# LCD.net
KiCad netlist of a schematic drawn in Altium Designer
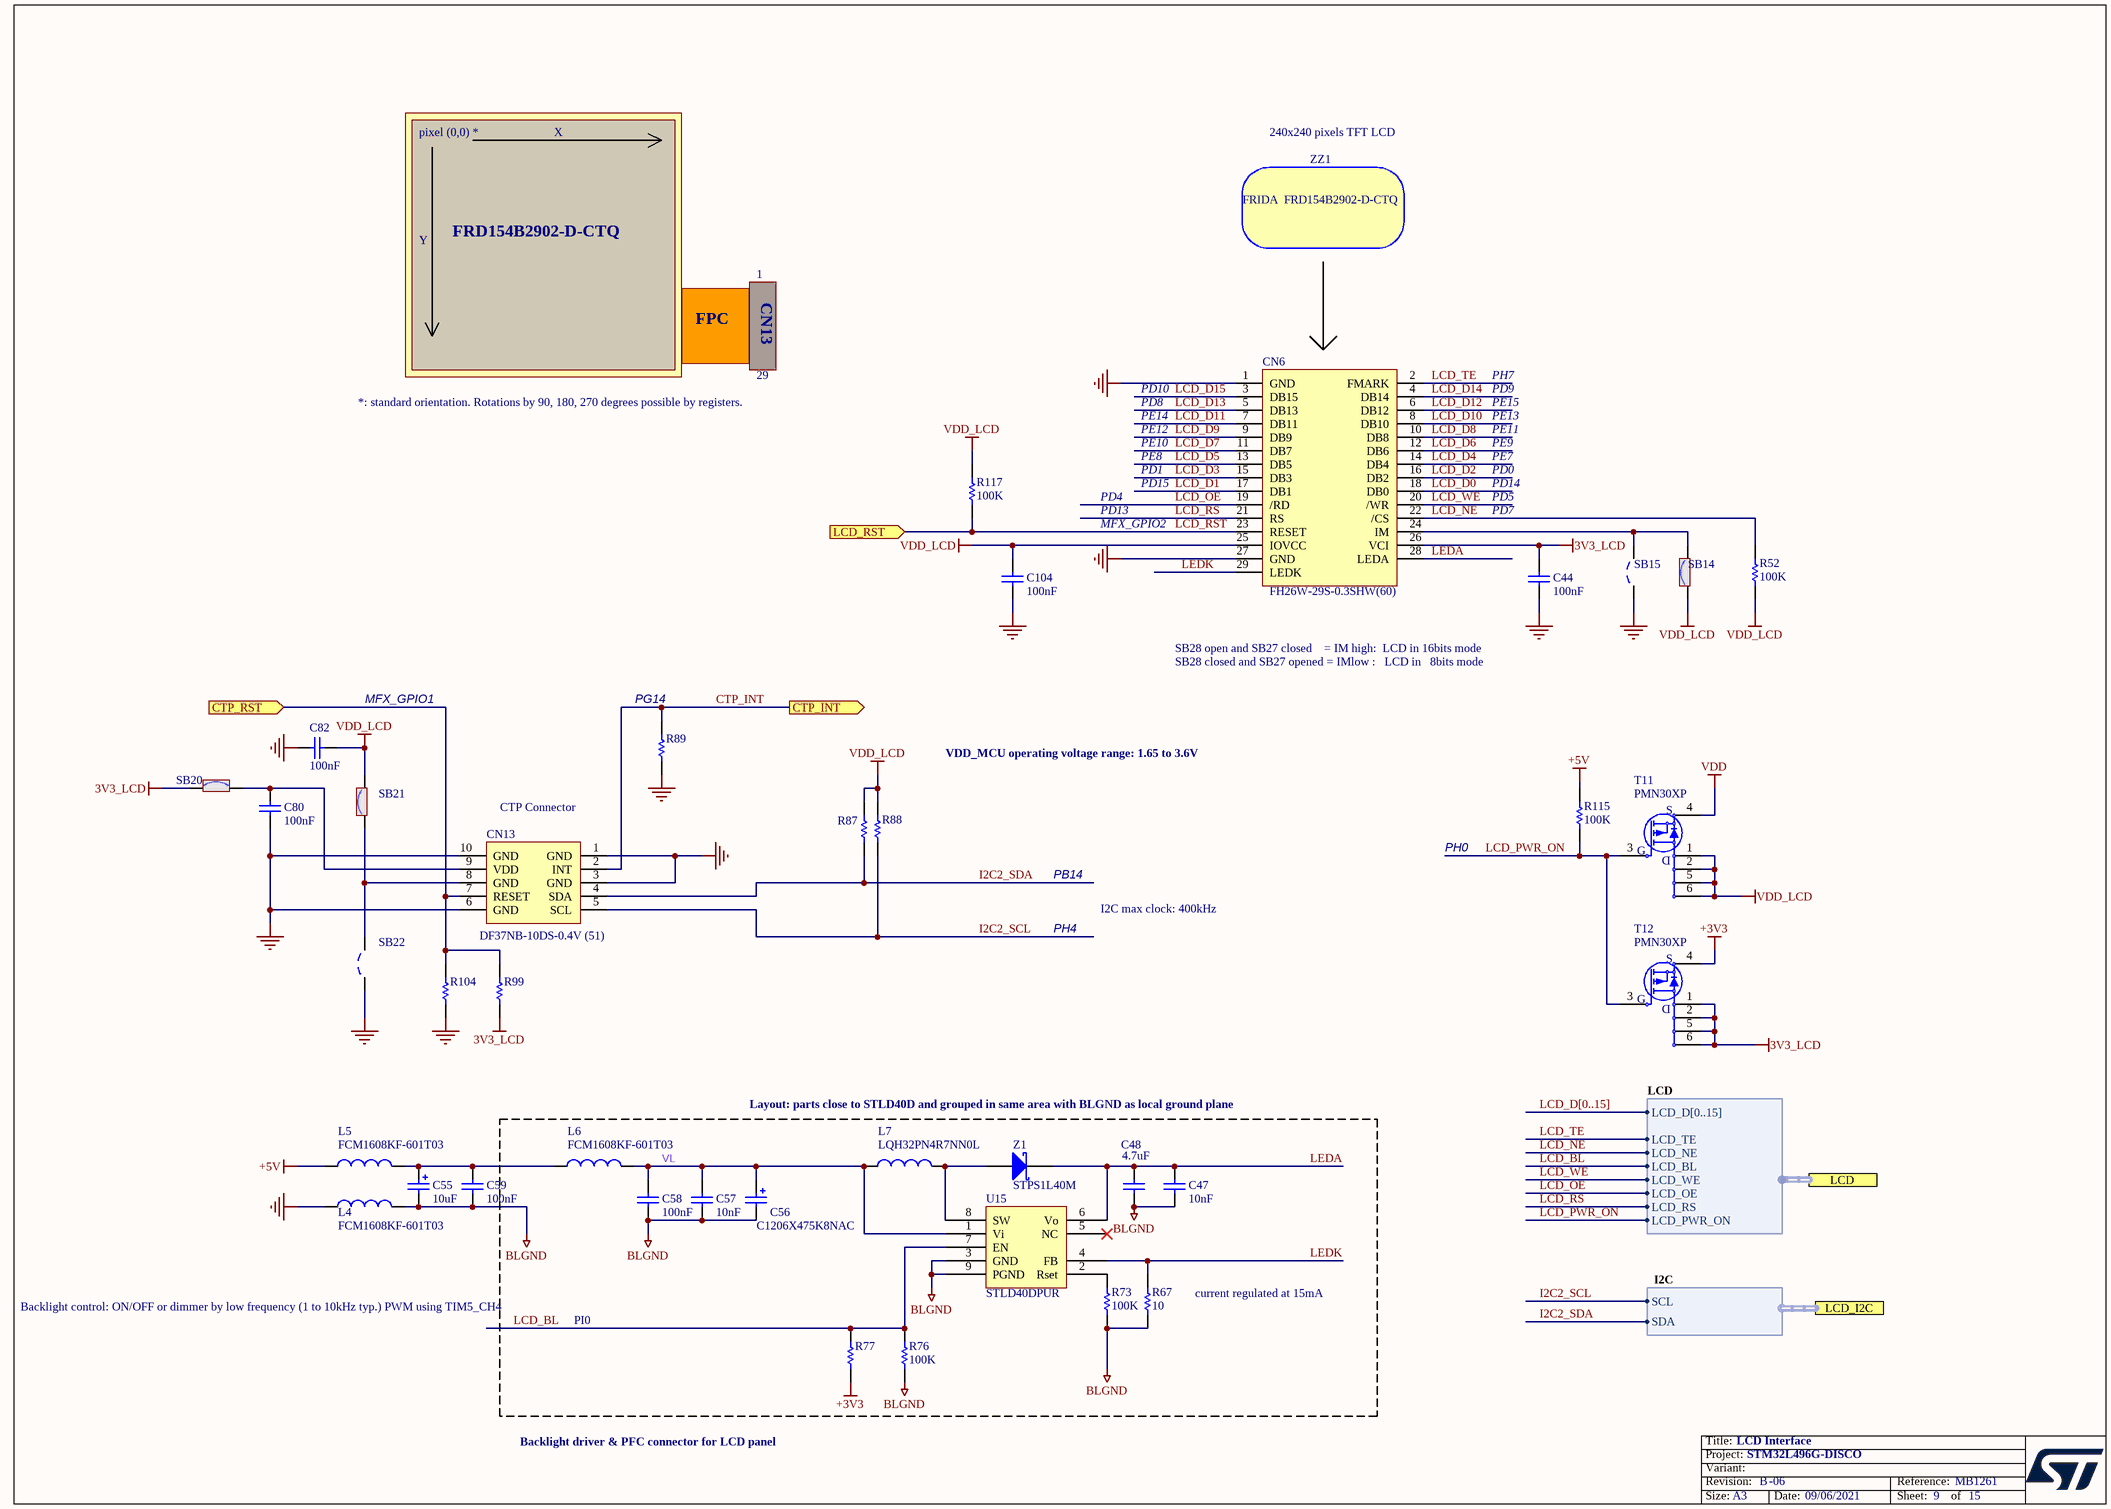
[diagram p0: LCD.SchDoc]

(export (version "E")
  (design (tool "Eeschema 10.0.6"))
  (components
    (comp (ref "C44")
      (value "100nF")
      (footprint "0603C")
      (description "Capacitor,100nF,10%,16V,X7R,0603,YAGEO")
      (fields (field (name "Comment") "CC0603KRX7R7BB104") (field (name "PUBLISHER") "Altium Limited"))
      (libsource (lib "Miscellaneous Devices") (part "Cap"))
    )
    (comp (ref "C47")
      (value "10nF")
      (footprint "0603C")
      (description "Capacitor,10nF,0603,50V,10%,X7R,YAGEO;")
      (fields (field (name "Comment") "CC0603KRX7R9BB103") (field (name "PUBLISHER") "Altium Limited"))
      (libsource (lib "Miscellaneous Devices") (part "Cap"))
    )
    (comp (ref "C48")
      (value "4.7uF")
      (footprint "1206C")
      (description "Capacitor,4.7uF,50V,X7R,10%,1206")
      (fields (field (name "Comment") "CC1206KKX7R9BB475") (field (name "PUBLISHER") "Altium Limited"))
      (libsource (lib "Miscellaneous Devices") (part "CAP"))
    )
    (comp (ref "C55")
      (value "10uF")
      (footprint "TAN-A")
      (description "TAN Capacitor,10uF,10%,16V,A Type,AVX")
      (fields (field (name "Comment") "TAJA106K016R") (field (name "PUBLISHER") "Altium Limited"))
      (libsource (lib "Miscellaneous Devices") (part "Cap Pol1"))
    )
    (comp (ref "C56")
      (value "C1206X475K8NAC")
      (footprint "1206C")
      (description "Capacitor,4.7uF,±10%,X7R,10V,1206,C1206X475K8NAC")
      (fields (field (name "PUBLISHER") "Altium Limited"))
      (libsource (lib "Miscellaneous Devices") (part "Cap Pol1"))
    )
    (comp (ref "C57")
      (value "10nF")
      (footprint "0603C")
      (description "Capacitor,10nF,0603,50V,10%,X7R,YAGEO;")
      (fields (field (name "Comment") "CC0603KRX7R9BB103") (field (name "PUBLISHER") "Altium Limited"))
      (libsource (lib "Miscellaneous Devices") (part "Cap"))
    )
    (comp (ref "C58")
      (value "100nF")
      (footprint "0603C")
      (description "Capacitor,100nF,10%,16V,X7R,0603,YAGEO")
      (fields (field (name "Comment") "CC0603KRX7R7BB104") (field (name "PUBLISHER") "Altium Limited"))
      (libsource (lib "Miscellaneous Devices") (part "Cap"))
    )
    (comp (ref "C59")
      (value "100nF")
      (footprint "0603C")
      (description "Capacitor,100nF,10%,16V,X7R,0603,YAGEO")
      (fields (field (name "Comment") "CC0603KRX7R7BB104") (field (name "PUBLISHER") "Altium Limited"))
      (libsource (lib "Miscellaneous Devices") (part "Cap"))
    )
    (comp (ref "C80")
      (value "100nF")
      (footprint "0603C")
      (description "Capacitor,100nF,10%,16V,X7R,0603,YAGEO")
      (fields (field (name "Comment") "CC0603KRX7R7BB104") (field (name "PUBLISHER") "Altium Limited"))
      (libsource (lib "Miscellaneous Devices") (part "Cap"))
    )
    (comp (ref "C82")
      (value "100nF")
      (footprint "0603C")
      (description "Capacitor,100nF,10%,16V,X7R,0603,YAGEO")
      (fields (field (name "Comment") "CC0603KRX7R7BB104") (field (name "PUBLISHER") "Altium Limited"))
      (libsource (lib "Miscellaneous Devices") (part "Cap"))
    )
    (comp (ref "C104")
      (value "100nF")
      (footprint "0603C")
      (description "Capacitor,100nF,10%,16V,X7R,0603,YAGEO")
      (fields (field (name "Comment") "CC0603KRX7R7BB104") (field (name "PUBLISHER") "Altium Limited"))
      (libsource (lib "Miscellaneous Devices") (part "Cap"))
    )
    (comp (ref "CN6")
      (value "FH26W-29S-0.3SHW(60)")
      (footprint "FH26-29S-0R3SHW")
      (description "29pins FPC connector")
      (libsource (lib "MB1209_3") (part "FH26-29S-0.3SHW"))
    )
    (comp (ref "CN13")
      (value "DF37NB-10DS-0.4V (51)")
      (footprint "DF37NB-10DS-0R4V")
      (description "Header, 5-Pin, Dual row")
      (fields (field (name "PUBLISHER") "Altium Limited"))
      (libsource (lib "MB1209") (part "Header 5X2A"))
    )
    (comp (ref "L4")
      (value "FCM1608KF-601T03")
      (footprint "0603L")
      (description "100uH Bead")
      (fields (field (name "PUBLISHER") "Altium Limited"))
      (libsource (lib "Miscellaneous Devices") (part "Inductor"))
    )
    (comp (ref "L5")
      (value "FCM1608KF-601T03")
      (footprint "0603L")
      (description "100uH Bead")
      (fields (field (name "PUBLISHER") "Altium Limited"))
      (libsource (lib "Miscellaneous Devices") (part "Inductor"))
    )
    (comp (ref "L6")
      (value "FCM1608KF-601T03")
      (footprint "0603L")
      (description "100uH Bead")
      (fields (field (name "PUBLISHER") "Altium Limited"))
      (libsource (lib "Miscellaneous Devices") (part "Inductor"))
    )
    (comp (ref "L7")
      (value "LQH32PN4R7NN0L")
      (footprint "1210L")
      (description "IND,4.7uH,1A,1210,LQH32PN4R7NN0L")
      (fields (field (name "PUBLISHER") "Altium Limited"))
      (libsource (lib "Miscellaneous Devices") (part "Inductor"))
    )
    (comp (ref "R52")
      (value "100K")
      (footprint "0603R")
      (description "Resistor,100K,0603,1%,YAGEO")
      (fields (field (name "Comment") "RC0603FR-07100KL") (field (name "PUBLISHER") "Altium Limited"))
      (libsource (lib "Miscellaneous Devices") (part "res1"))
    )
    (comp (ref "R67")
      (value "10")
      (footprint "0603R")
      (description "Resistor,10R,0603,1%,YAGEO")
      (fields (field (name "Comment") "RC0603FR-0710RL") (field (name "PUBLISHER") "Altium Limited"))
      (libsource (lib "Miscellaneous Devices") (part "res1"))
    )
    (comp (ref "R73")
      (value "100K")
      (footprint "0603R")
      (description "Resistor,100K,0603,1%,YAGEO")
      (fields (field (name "Comment") "RC0603FR-07100KL") (field (name "PUBLISHER") "Altium Limited"))
      (libsource (lib "Miscellaneous Devices") (part "res1"))
    )
    (comp (ref "R76")
      (value "100K")
      (footprint "0603R")
      (description "Resistor,100K,0603,1%,YAGEO")
      (fields (field (name "Comment") "RC0603FR-07100KL") (field (name "PUBLISHER") "Altium Limited"))
      (libsource (lib "Miscellaneous Devices") (part "res1"))
    )
    (comp (ref "R77")
      (value "~")
      (footprint "0603R")
      (description "Resistor,100K,0603,1%,YAGEO")
      (fields (field (name "PUBLISHER") "Altium Limited"))
      (libsource (lib "Miscellaneous Devices") (part "res1"))
    )
    (comp (ref "R87")
      (value "~")
      (footprint "0603R")
      (description "Resistor,1.5K,0603,1%,YAGEO")
      (fields (field (name "PUBLISHER") "Altium Limited"))
      (libsource (lib "Miscellaneous Devices") (part "res1"))
    )
    (comp (ref "R88")
      (value "~")
      (footprint "0603R")
      (description "Resistor,1.5K,0603,1%,YAGEO")
      (fields (field (name "PUBLISHER") "Altium Limited"))
      (libsource (lib "Miscellaneous Devices") (part "res1"))
    )
    (comp (ref "R89")
      (value "~")
      (footprint "0603R")
      (description "Resistor,100K,0603,1%,YAGEO")
      (fields (field (name "PUBLISHER") "Altium Limited"))
      (libsource (lib "Miscellaneous Devices") (part "res1"))
    )
    (comp (ref "R99")
      (value "~")
      (footprint "0603R")
      (description "Resistor,100K,0603,1%,YAGEO")
      (fields (field (name "PUBLISHER") "Altium Limited"))
      (libsource (lib "Miscellaneous Devices") (part "res1"))
    )
    (comp (ref "R104")
      (value "~")
      (footprint "0603R")
      (description "Resistor,100K,0603,1%,YAGEO")
      (fields (field (name "PUBLISHER") "Altium Limited"))
      (libsource (lib "Miscellaneous Devices") (part "res1"))
    )
    (comp (ref "R115")
      (value "100K")
      (footprint "0603R")
      (description "Resistor,100K,0603,1%,YAGEO")
      (fields (field (name "Comment") "RC0603FR-07100KL") (field (name "PUBLISHER") "Altium Limited"))
      (libsource (lib "Miscellaneous Devices") (part "res1"))
    )
    (comp (ref "R117")
      (value "100K")
      (footprint "0603R")
      (description "Resistor,100K,0603,1%,YAGEO")
      (fields (field (name "Comment") "RC0603FR-07100KL") (field (name "PUBLISHER") "Altium Limited"))
      (libsource (lib "Miscellaneous Devices") (part "res1"))
    )
    (comp (ref "SB14") (value "Solder Bridge ON") (footprint "SB_0603") (libsource (lib "") (part "SB_ON_1")))
    (comp (ref "SB15")
      (value "Solder Bridge OFF")
      (footprint "SB_0603")
      (libsource (lib "MCD_TOOLS") (part "SB_OFF"))
    )
    (comp (ref "SB20")
      (value "Solder Bridge ON")
      (footprint "SB_0603")
      (libsource (lib "MCD_TOOLS") (part "SB_ON"))
    )
    (comp (ref "SB21") (value "Solder Bridge ON") (footprint "SB_0603") (libsource (lib "") (part "SB_ON_1")))
    (comp (ref "SB22")
      (value "Solder Bridge OFF")
      (footprint "SB_0603")
      (libsource (lib "MCD_TOOLS") (part "SB_OFF"))
    )
    (comp (ref "T11")
      (value "PMN30XP")
      (footprint "MOS_SOT23-6L")
      (description "20 V, P-channel Trench MOSFET")
      (fields (field (name "INTERNAL_PART_NUMBER") "MCD-01926") (field (name "MANUFACTURER") "NEXPERIA"))
      (libsource (lib "MCD_PARTS_database") (part "PMN30XP"))
    )
    (comp (ref "T12")
      (value "PMN30XP")
      (footprint "MOS_SOT23-6L")
      (description "20 V, P-channel Trench MOSFET")
      (fields (field (name "INTERNAL_PART_NUMBER") "MCD-01926") (field (name "MANUFACTURER") "NEXPERIA"))
      (libsource (lib "MCD_PARTS_database") (part "PMN30XP"))
    )
    (comp (ref "U15")
      (value "STLD40DPUR")
      (footprint "SON8_0R65_3X3")
      (libsource (lib "3.2LCD_daughterboard") (part "STLD40DPMR"))
    )
    (comp (ref "Z1")
      (value "STPS1L40M")
      (footprint "DO-216AA")
      (description "Schottky Diode")
      (fields (field (name "PUBLISHER") "Altium Limited"))
      (libsource (lib "Miscellaneous Devices") (part "D Schottky"))
    )
    (comp (ref "ZZ1")
      (value "FRIDA  FRD154B2902-D-CTQ")
      (footprint "LCD_FRD154BP2902-CTP")
      (libsource (lib "Almos") (part "BoM_Item"))
    )
  )
  (nets
    (net (code "3") (name "+3V3") (class "Default")
      (node (ref "R77") (pin "2") (pinfunction "2_2") (pintype "passive"))
      (node (ref "T12") (pin "4") (pinfunction "S_4") (pintype "passive"))
    )
    (net (code "4") (name "+5V") (class "Default")
      (node (ref "L5") (pin "1") (pinfunction "1_1") (pintype "passive"))
      (node (ref "R115") (pin "1") (pinfunction "1_1") (pintype "passive"))
    )
    (net (code "5") (name "/CTP_INT") (class "Default")
      (node (ref "CN13") (pin "2") (pinfunction "INT_2") (pintype "passive"))
      (node (ref "R89") (pin "1") (pinfunction "1_1") (pintype "passive"))
    )
    (net (code "6") (name "/CTP_RST") (class "Default")
      (node (ref "CN13") (pin "7") (pinfunction "RESET_7") (pintype "passive"))
      (node (ref "R104") (pin "1") (pinfunction "1_1") (pintype "passive"))
      (node (ref "R99") (pin "1") (pinfunction "1_1") (pintype "passive"))
    )
    (net (code "7") (name "/I2C2_SCL") (class "Default")
      (node (ref "CN13") (pin "5") (pinfunction "SCL_5") (pintype "passive"))
      (node (ref "R88") (pin "2") (pinfunction "2_2") (pintype "passive"))
    )
    (net (code "8") (name "/I2C2_SDA") (class "Default")
      (node (ref "CN13") (pin "4") (pinfunction "SDA_4") (pintype "passive"))
      (node (ref "R87") (pin "1") (pinfunction "1_1") (pintype "passive"))
    )
    (net (code "9") (name "/LCD_BL") (class "Default")
      (node (ref "R76") (pin "1") (pinfunction "1_1") (pintype "passive"))
      (node (ref "R77") (pin "1") (pinfunction "1_1") (pintype "passive"))
      (node (ref "U15") (pin "7") (pinfunction "EN_7") (pintype "passive"))
    )
    (net (code "10") (name "/LCD_D0") (class "Default")
      (node (ref "CN6") (pin "18") (pinfunction "DB0_18") (pintype "passive"))
    )
    (net (code "11") (name "/LCD_D1") (class "Default")
      (node (ref "CN6") (pin "17") (pinfunction "DB1_17") (pintype "passive"))
    )
    (net (code "12") (name "/LCD_D2") (class "Default")
      (node (ref "CN6") (pin "16") (pinfunction "DB2_16") (pintype "passive"))
    )
    (net (code "13") (name "/LCD_D3") (class "Default")
      (node (ref "CN6") (pin "15") (pinfunction "DB3_15") (pintype "passive"))
    )
    (net (code "14") (name "/LCD_D4") (class "Default")
      (node (ref "CN6") (pin "14") (pinfunction "DB4_14") (pintype "passive"))
    )
    (net (code "15") (name "/LCD_D5") (class "Default")
      (node (ref "CN6") (pin "13") (pinfunction "DB5_13") (pintype "passive"))
    )
    (net (code "16") (name "/LCD_D6") (class "Default")
      (node (ref "CN6") (pin "12") (pinfunction "DB6_12") (pintype "passive"))
    )
    (net (code "17") (name "/LCD_D7") (class "Default")
      (node (ref "CN6") (pin "11") (pinfunction "DB7_11") (pintype "passive"))
    )
    (net (code "18") (name "/LCD_D8") (class "Default")
      (node (ref "CN6") (pin "10") (pinfunction "DB8_10") (pintype "passive"))
    )
    (net (code "19") (name "/LCD_D9") (class "Default")
      (node (ref "CN6") (pin "9") (pinfunction "DB9_9") (pintype "passive"))
    )
    (net (code "20") (name "/LCD_D10") (class "Default")
      (node (ref "CN6") (pin "8") (pinfunction "DB10_8") (pintype "passive"))
    )
    (net (code "21") (name "/LCD_D11") (class "Default")
      (node (ref "CN6") (pin "7") (pinfunction "DB11_7") (pintype "passive"))
    )
    (net (code "22") (name "/LCD_D12") (class "Default")
      (node (ref "CN6") (pin "6") (pinfunction "DB12_6") (pintype "passive"))
    )
    (net (code "23") (name "/LCD_D13") (class "Default")
      (node (ref "CN6") (pin "5") (pinfunction "DB13_5") (pintype "passive"))
    )
    (net (code "24") (name "/LCD_D14") (class "Default")
      (node (ref "CN6") (pin "4") (pinfunction "DB14_4") (pintype "passive"))
    )
    (net (code "25") (name "/LCD_D15") (class "Default")
      (node (ref "CN6") (pin "3") (pinfunction "DB15_3") (pintype "passive"))
    )
    (net (code "27") (name "/LCD_NE") (class "Default")
      (node (ref "CN6") (pin "22") (pinfunction "/CS_22") (pintype "passive"))
      (node (ref "R52") (pin "1") (pinfunction "1_1") (pintype "passive"))
    )
    (net (code "28") (name "/LCD_OE") (class "Default")
      (node (ref "CN6") (pin "19") (pinfunction "/RD_19") (pintype "passive"))
    )
    (net (code "29") (name "/LCD_PWR_ON") (class "Default")
      (node (ref "R115") (pin "2") (pinfunction "2_2") (pintype "passive"))
      (node (ref "T11") (pin "3") (pinfunction "G_3") (pintype "passive"))
      (node (ref "T12") (pin "3") (pinfunction "G_3") (pintype "passive"))
    )
    (net (code "30") (name "/LCD_RS") (class "Default")
      (node (ref "CN6") (pin "21") (pinfunction "RS_21") (pintype "passive"))
    )
    (net (code "31") (name "/LCD_RST") (class "Default")
      (node (ref "CN6") (pin "23") (pinfunction "RESET_23") (pintype "passive"))
      (node (ref "R117") (pin "2") (pinfunction "2_2") (pintype "passive"))
    )
    (net (code "32") (name "/LCD_TE") (class "Default")
      (node (ref "CN6") (pin "2") (pinfunction "FMARK_2") (pintype "passive"))
    )
    (net (code "33") (name "/LCD_WE") (class "Default")
      (node (ref "CN6") (pin "20") (pinfunction "/WR_20") (pintype "passive"))
    )
    (net (code "34") (name "/LEDA") (class "Default")
      (node (ref "C47") (pin "1") (pinfunction "1_1") (pintype "passive"))
      (node (ref "C48") (pin "1") (pinfunction "1_1") (pintype "passive"))
      (node (ref "CN6") (pin "28") (pinfunction "LEDA_28") (pintype "passive"))
      (node (ref "U15") (pin "6") (pinfunction "Vo_6") (pintype "passive"))
      (node (ref "Z1") (pin "2") (pinfunction "K_2") (pintype "passive"))
    )
    (net (code "35") (name "/LEDK") (class "Default")
      (node (ref "CN6") (pin "29") (pinfunction "LEDK_29") (pintype "passive"))
      (node (ref "R67") (pin "1") (pinfunction "1_1") (pintype "passive"))
      (node (ref "U15") (pin "4") (pinfunction "FB_4") (pintype "passive"))
    )
    (net (code "36") (name "/VL") (class "Default")
      (node (ref "C56") (pin "1") (pinfunction "1_1") (pintype "passive"))
      (node (ref "C57") (pin "1") (pinfunction "1_1") (pintype "passive"))
      (node (ref "C58") (pin "1") (pinfunction "1_1") (pintype "passive"))
      (node (ref "L6") (pin "2") (pinfunction "2_2") (pintype "passive"))
      (node (ref "L7") (pin "1") (pinfunction "1_1") (pintype "passive"))
      (node (ref "U15") (pin "1") (pinfunction "Vi_1") (pintype "passive"))
    )
    (net (code "39") (name "3V3_LCD") (class "Default")
      (node (ref "C44") (pin "1") (pinfunction "1_1") (pintype "passive"))
      (node (ref "CN6") (pin "26") (pinfunction "VCI_26") (pintype "passive"))
      (node (ref "R99") (pin "2") (pinfunction "2_2") (pintype "passive"))
      (node (ref "SB20") (pin "1") (pinfunction "1_1") (pintype "passive"))
      (node (ref "T12") (pin "1") (pinfunction "S_1") (pintype "passive"))
      (node (ref "T12") (pin "2") (pinfunction "S_2") (pintype "passive"))
      (node (ref "T12") (pin "5") (pinfunction "D_5") (pintype "passive"))
      (node (ref "T12") (pin "6") (pinfunction "D_6") (pintype "passive"))
    )
    (net (code "40") (name "BLGND") (class "Default")
      (node (ref "C47") (pin "2") (pinfunction "2_2") (pintype "passive"))
      (node (ref "C48") (pin "2") (pinfunction "2_2") (pintype "passive"))
      (node (ref "C55") (pin "2") (pinfunction "2_2") (pintype "passive"))
      (node (ref "C56") (pin "2") (pinfunction "2_2") (pintype "passive"))
      (node (ref "C57") (pin "2") (pinfunction "2_2") (pintype "passive"))
      (node (ref "C58") (pin "2") (pinfunction "2_2") (pintype "passive"))
      (node (ref "C59") (pin "2") (pinfunction "2_2") (pintype "passive"))
      (node (ref "L4") (pin "2") (pinfunction "2_2") (pintype "passive"))
      (node (ref "R67") (pin "2") (pinfunction "2_2") (pintype "passive"))
      (node (ref "R73") (pin "2") (pinfunction "2_2") (pintype "passive"))
      (node (ref "R76") (pin "2") (pinfunction "2_2") (pintype "passive"))
      (node (ref "U15") (pin "3") (pinfunction "GND_3") (pintype "passive"))
      (node (ref "U15") (pin "9") (pinfunction "PGND_9") (pintype "passive"))
    )
    (net (code "41") (name "GND") (class "Default")
      (node (ref "C104") (pin "2") (pinfunction "2_2") (pintype "passive"))
      (node (ref "C44") (pin "2") (pinfunction "2_2") (pintype "passive"))
      (node (ref "C80") (pin "2") (pinfunction "2_2") (pintype "passive"))
      (node (ref "C82") (pin "2") (pinfunction "2_2") (pintype "passive"))
      (node (ref "CN13") (pin "1") (pinfunction "GND_1") (pintype "passive"))
      (node (ref "CN13") (pin "10") (pinfunction "GND_10") (pintype "passive"))
      (node (ref "CN13") (pin "3") (pinfunction "GND_3") (pintype "passive"))
      (node (ref "CN13") (pin "6") (pinfunction "GND_6") (pintype "passive"))
      (node (ref "CN6") (pin "1") (pinfunction "GND_1") (pintype "passive"))
      (node (ref "CN6") (pin "27") (pinfunction "GND_27") (pintype "passive"))
      (node (ref "L4") (pin "1") (pinfunction "1_1") (pintype "passive"))
      (node (ref "R104") (pin "2") (pinfunction "2_2") (pintype "passive"))
      (node (ref "R89") (pin "2") (pinfunction "2_2") (pintype "passive"))
      (node (ref "SB15") (pin "1") (pinfunction "1_1") (pintype "passive"))
      (node (ref "SB22") (pin "1") (pinfunction "1_1") (pintype "passive"))
    )
    (net (code "42") (name "Net-(C55-Pad1)") (class "Default")
      (node (ref "C55") (pin "1") (pinfunction "1_1") (pintype "passive"))
      (node (ref "C59") (pin "1") (pinfunction "1_1") (pintype "passive"))
      (node (ref "L5") (pin "2") (pinfunction "2_2") (pintype "passive"))
      (node (ref "L6") (pin "1") (pinfunction "1_1") (pintype "passive"))
    )
    (net (code "43") (name "Net-(CN6-IM)") (class "Default")
      (node (ref "CN6") (pin "24") (pinfunction "IM_24") (pintype "passive"))
      (node (ref "SB14") (pin "2") (pinfunction "2_2") (pintype "passive"))
      (node (ref "SB15") (pin "2") (pinfunction "2_2") (pintype "passive"))
    )
    (net (code "44") (name "Net-(CN13-GND-Pad8)") (class "Default")
      (node (ref "CN13") (pin "8") (pinfunction "GND_8") (pintype "passive"))
      (node (ref "SB21") (pin "1") (pinfunction "1_1") (pintype "passive"))
      (node (ref "SB22") (pin "2") (pinfunction "2_2") (pintype "passive"))
    )
    (net (code "45") (name "Net-(CN13-VDD)") (class "Default")
      (node (ref "C80") (pin "1") (pinfunction "1_1") (pintype "passive"))
      (node (ref "CN13") (pin "9") (pinfunction "VDD_9") (pintype "passive"))
      (node (ref "SB20") (pin "2") (pinfunction "2_2") (pintype "passive"))
    )
    (net (code "46") (name "Net-(U15-Rset)") (class "Default")
      (node (ref "R73") (pin "1") (pinfunction "1_1") (pintype "passive"))
      (node (ref "U15") (pin "2") (pinfunction "Rset_2") (pintype "passive"))
    )
    (net (code "47") (name "Net-(U15-SW)") (class "Default")
      (node (ref "L7") (pin "2") (pinfunction "2_2") (pintype "passive"))
      (node (ref "U15") (pin "8") (pinfunction "SW_8") (pintype "passive"))
      (node (ref "Z1") (pin "1") (pinfunction "A_1") (pintype "passive"))
    )
    (net (code "48") (name "VDD") (class "Default")
      (node (ref "T11") (pin "4") (pinfunction "S_4") (pintype "passive"))
    )
    (net (code "49") (name "VDD_LCD") (class "Default")
      (node (ref "C104") (pin "1") (pinfunction "1_1") (pintype "passive"))
      (node (ref "C82") (pin "1") (pinfunction "1_1") (pintype "passive"))
      (node (ref "CN6") (pin "25") (pinfunction "IOVCC_25") (pintype "passive"))
      (node (ref "R117") (pin "1") (pinfunction "1_1") (pintype "passive"))
      (node (ref "R52") (pin "2") (pinfunction "2_2") (pintype "passive"))
      (node (ref "R87") (pin "2") (pinfunction "2_2") (pintype "passive"))
      (node (ref "R88") (pin "1") (pinfunction "1_1") (pintype "passive"))
      (node (ref "SB14") (pin "1") (pinfunction "1_1") (pintype "passive"))
      (node (ref "SB21") (pin "2") (pinfunction "2_2") (pintype "passive"))
      (node (ref "T11") (pin "1") (pinfunction "S_1") (pintype "passive"))
      (node (ref "T11") (pin "2") (pinfunction "S_2") (pintype "passive"))
      (node (ref "T11") (pin "5") (pinfunction "D_5") (pintype "passive"))
      (node (ref "T11") (pin "6") (pinfunction "D_6") (pintype "passive"))
    )
    (net (code "50") (name "unconnected-(U15-NC-Pad5)") (class "Default")
      (node (ref "U15") (pin "5") (pinfunction "NC_5") (pintype "passive+no_connect"))
    )
  )
)
